# STM32_FillLab_WalkThrough.net
KiCad netlist of a schematic drawn in Altium Designer
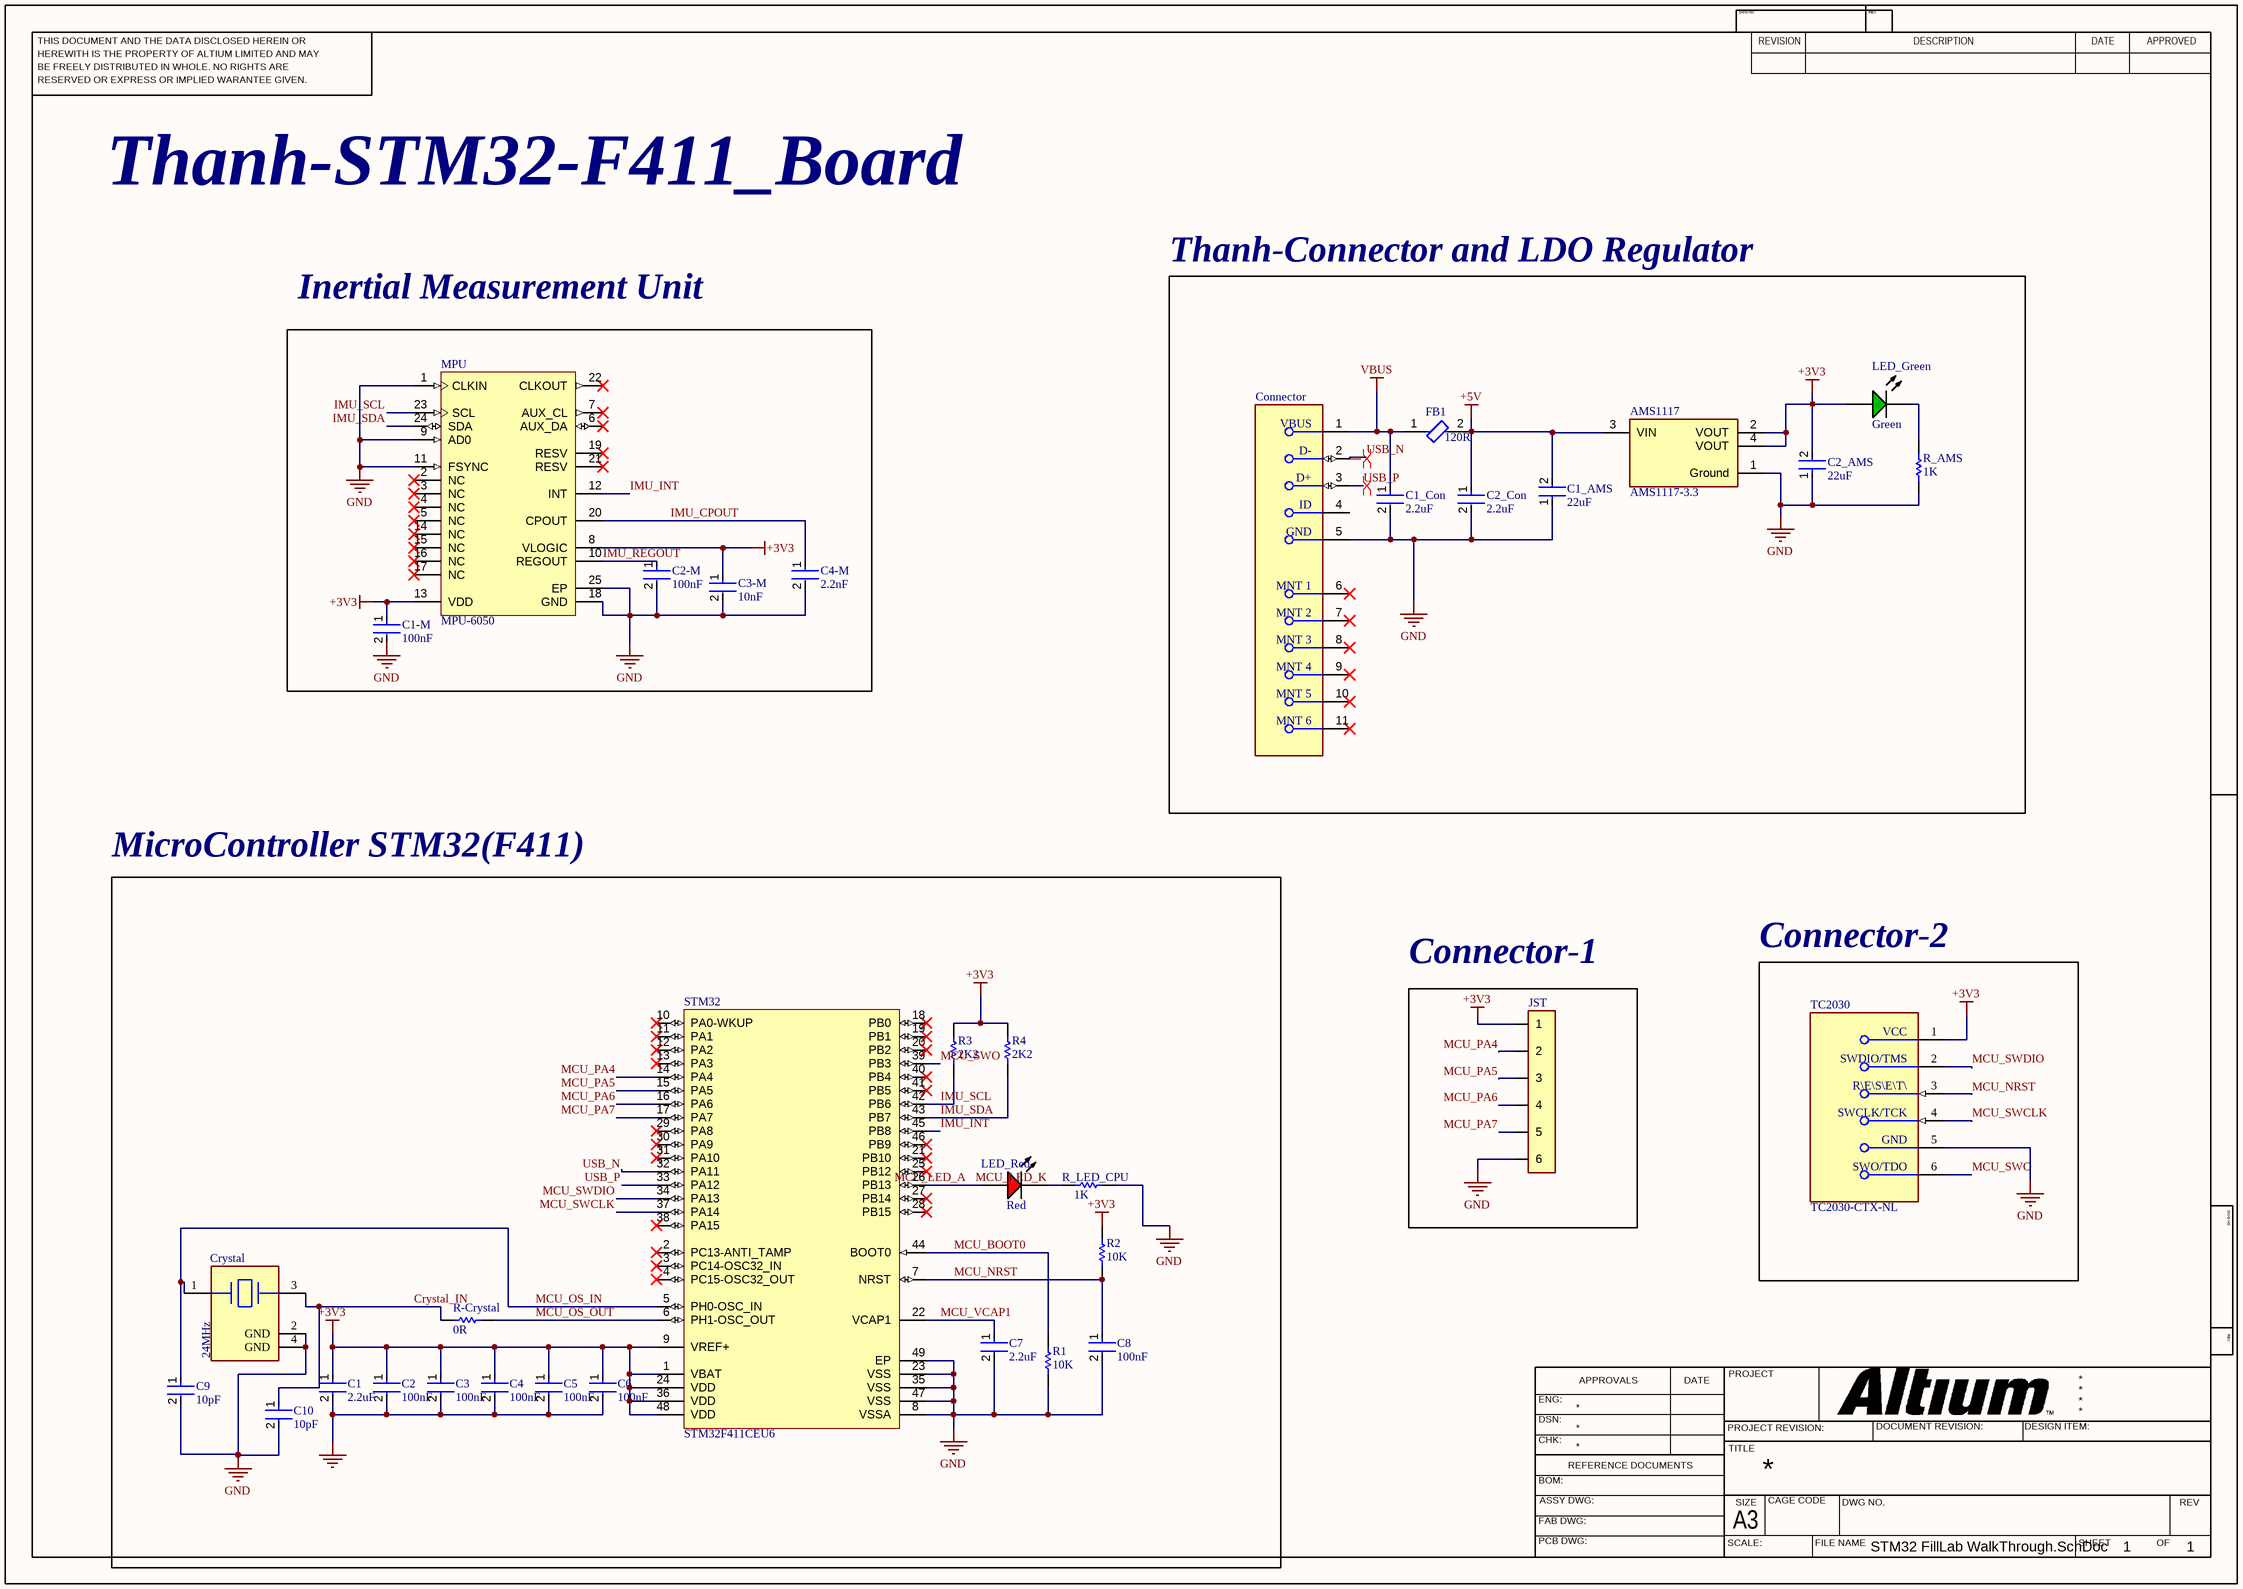
[diagram p0: STM32 FillLab WalkThrough.SchDoc]

(export (version "E")
  (design (tool "Eeschema 10.0.6"))
  (components
    (comp (ref "AMS1117")
      (value "AMS1117-3.3")
      (footprint "FP-AMS1117-IPC_C")
      (description "LDO Voltage Regulators 1A, 3.3V")
      (fields
        (field (name "OCTOPART") "https://octopart.com/ams1117-3.3-advanced+monolithic+systems-25899300")
        (field (name "MANUFACTURER") "Advanced Monolithic Systems")
      )
      (libsource (lib "Altium Content Vault") (part "8bdbb5f8e77002000e30dd2845d0354"))
    )
    (comp (ref "C1")
      (value "2.2uF")
      (footprint "FP-C0402-BB-MFG")
      (description "CAP CER 0.1UF 10V X5R 0402")
      (fields (field (name "MANUFACTURER") "Kemet") (field (name "TOLERANCE") "0.1"))
      (libsource (lib "Altium Content Vault") (part "b4654b650e69147ec39a6b967a45e02"))
    )
    (comp (ref "C1-M")
      (value "100nF")
      (footprint "FP-C0402-BB-MFG")
      (description "CAP CER 0.1UF 10V X5R 0402")
      (fields (field (name "MANUFACTURER") "Kemet") (field (name "TOLERANCE") "0.1"))
      (libsource (lib "Altium Content Vault") (part "b4654b650e69147ec39a6b967a45e02"))
    )
    (comp (ref "C1_AMS")
      (value "22uF")
      (footprint "FP-C0402-BB-MFG")
      (description "CAP CER 0.1UF 10V X5R 0402")
      (fields (field (name "MANUFACTURER") "Kemet") (field (name "TOLERANCE") "0.1"))
      (libsource (lib "Altium Content Vault") (part "b4654b650e69147ec39a6b967a45e02"))
    )
    (comp (ref "C1_Con")
      (value "2.2uF")
      (footprint "FP-C0402-BB-MFG")
      (description "CAP CER 0.1UF 10V X5R 0402")
      (fields (field (name "MANUFACTURER") "Kemet") (field (name "TOLERANCE") "0.1"))
      (libsource (lib "Altium Content Vault") (part "b4654b650e69147ec39a6b967a45e02"))
    )
    (comp (ref "C2")
      (value "100nF")
      (footprint "FP-C0402-BB-MFG")
      (description "CAP CER 0.1UF 10V X5R 0402")
      (fields (field (name "MANUFACTURER") "Kemet") (field (name "TOLERANCE") "0.1"))
      (libsource (lib "Altium Content Vault") (part "b4654b650e69147ec39a6b967a45e02"))
    )
    (comp (ref "C2-M")
      (value "100nF")
      (footprint "FP-C0402-BB-MFG")
      (description "CAP CER 0.1UF 10V X5R 0402")
      (fields (field (name "MANUFACTURER") "Kemet") (field (name "TOLERANCE") "0.1"))
      (libsource (lib "Altium Content Vault") (part "b4654b650e69147ec39a6b967a45e02"))
    )
    (comp (ref "C2_AMS")
      (value "22uF")
      (footprint "FP-C0402-BB-MFG")
      (description "CAP CER 0.1UF 10V X5R 0402")
      (fields (field (name "MANUFACTURER") "Kemet") (field (name "TOLERANCE") "0.1"))
      (libsource (lib "Altium Content Vault") (part "b4654b650e69147ec39a6b967a45e02"))
    )
    (comp (ref "C2_Con")
      (value "2.2uF")
      (footprint "FP-C0402-BB-MFG")
      (description "CAP CER 0.1UF 10V X5R 0402")
      (fields (field (name "MANUFACTURER") "Kemet") (field (name "TOLERANCE") "0.1"))
      (libsource (lib "Altium Content Vault") (part "b4654b650e69147ec39a6b967a45e02"))
    )
    (comp (ref "C3")
      (value "100nF")
      (footprint "FP-C0402-BB-MFG")
      (description "CAP CER 0.1UF 10V X5R 0402")
      (fields (field (name "MANUFACTURER") "Kemet") (field (name "TOLERANCE") "0.1"))
      (libsource (lib "Altium Content Vault") (part "b4654b650e69147ec39a6b967a45e02"))
    )
    (comp (ref "C3-M")
      (value "10nF")
      (footprint "FP-C0402-BB-MFG")
      (description "CAP CER 0.1UF 10V X5R 0402")
      (fields (field (name "MANUFACTURER") "Kemet") (field (name "TOLERANCE") "0.1"))
      (libsource (lib "Altium Content Vault") (part "b4654b650e69147ec39a6b967a45e02"))
    )
    (comp (ref "C4")
      (value "100nF")
      (footprint "FP-C0402-BB-MFG")
      (description "CAP CER 0.1UF 10V X5R 0402")
      (fields (field (name "MANUFACTURER") "Kemet") (field (name "TOLERANCE") "0.1"))
      (libsource (lib "Altium Content Vault") (part "b4654b650e69147ec39a6b967a45e02"))
    )
    (comp (ref "C4-M")
      (value "2.2nF")
      (footprint "FP-C0402-BB-MFG")
      (description "CAP CER 0.1UF 10V X5R 0402")
      (fields (field (name "MANUFACTURER") "Kemet") (field (name "TOLERANCE") "0.1"))
      (libsource (lib "Altium Content Vault") (part "b4654b650e69147ec39a6b967a45e02"))
    )
    (comp (ref "C5")
      (value "100nF")
      (footprint "FP-C0402-BB-MFG")
      (description "CAP CER 0.1UF 10V X5R 0402")
      (fields (field (name "MANUFACTURER") "Kemet") (field (name "TOLERANCE") "0.1"))
      (libsource (lib "Altium Content Vault") (part "b4654b650e69147ec39a6b967a45e02"))
    )
    (comp (ref "C6")
      (value "100nF")
      (footprint "FP-C0402-BB-MFG")
      (description "CAP CER 0.1UF 10V X5R 0402")
      (fields (field (name "MANUFACTURER") "Kemet") (field (name "TOLERANCE") "0.1"))
      (libsource (lib "Altium Content Vault") (part "b4654b650e69147ec39a6b967a45e02"))
    )
    (comp (ref "C7")
      (value "2.2uF")
      (footprint "FP-C0402-BB-MFG")
      (description "CAP CER 0.1UF 10V X5R 0402")
      (fields (field (name "MANUFACTURER") "Kemet") (field (name "TOLERANCE") "0.1"))
      (libsource (lib "Altium Content Vault") (part "b4654b650e69147ec39a6b967a45e02"))
    )
    (comp (ref "C8")
      (value "100nF")
      (footprint "FP-C0402-BB-MFG")
      (description "CAP CER 0.1UF 10V X5R 0402")
      (fields (field (name "MANUFACTURER") "Kemet") (field (name "TOLERANCE") "0.1"))
      (libsource (lib "Altium Content Vault") (part "b4654b650e69147ec39a6b967a45e02"))
    )
    (comp (ref "C9")
      (value "10pF")
      (footprint "FP-C0402-BB-MFG")
      (description "CAP CER 0.1UF 10V X5R 0402")
      (fields (field (name "MANUFACTURER") "Kemet") (field (name "TOLERANCE") "0.1"))
      (libsource (lib "Altium Content Vault") (part "b4654b650e69147ec39a6b967a45e02"))
    )
    (comp (ref "C10")
      (value "10pF")
      (footprint "FP-C0402-BB-MFG")
      (description "CAP CER 0.1UF 10V X5R 0402")
      (fields (field (name "MANUFACTURER") "Kemet") (field (name "TOLERANCE") "0.1"))
      (libsource (lib "Altium Content Vault") (part "b4654b650e69147ec39a6b967a45e02"))
    )
    (comp (ref "Connector")
      (value "473460001")
      (footprint "FP-473460001-MFG")
      (description "CONN RCPT USB2.0 MICRO B SMD R/A")
      (fields
        (field (name "OCTOPART") "https://octopart.com/47346-0001-molex-7164928")
        (field (name "MANUFACTURER") "Molex")
      )
      (libsource (lib "Altium Content Vault") (part "53ae1f1d9b557310b43ca686e5bb76a"))
    )
    (comp (ref "Crystal")
      (value "24MHz")
      (footprint "FP-ABM8-MFG")
      (description "Crystal 24MHz ±20ppm 18pF SMD-4 3.2mm x 2.5mm")
      (fields (field (name "TOLERANCE") "20ppm"))
      (libsource (lib "Altium Content Vault") (part "dfdb7f9a12507849fb681da9a70121c"))
    )
    (comp (ref "FB1")
      (value "120R")
      (footprint "FP-BLM15-0_05-IPC_B")
      (description "Chip Ferrite Bead, 0402, 1000Ω @ 100MHz, 0.65Ω, 25%, 300mA")
      (fields (field (name "TOLERANCE") "25%"))
      (libsource (lib "Altium Content Vault") (part "5f30dd21d616792df468990f7003faa"))
    )
    (comp (ref "JST")
      (value "SM06B-GHS-TB")
      (footprint "JST-GH-6")
      (description "Connector Header Surface Mount, Right Angle 6 position 0.049 (1.25mm)")
      (fields (field (name "MF") "JST Sales"))
      (libsource (lib "SM06B-GHS-TB") (part "SM06B-GHS-TB"))
    )
    (comp (ref "LED_Green")
      (value "Green")
      (footprint "AVAG-HSMX-C170_V")
      (description "Chip LED, Green, 2.2 V, -40 to 85 degC, 2-Pin SMD, Pb-Free, Tape and Reel")
      (fields (field (name "MANUFACTURER") "Avago"))
      (libsource (lib "Altium Content Vault") (part "LED_GREEN_A1K2-2"))
    )
    (comp (ref "LED_Red")
      (value "Red")
      (footprint "AVAG-HSMX-C150_V")
      (description "LED Uni-Color Red, 65 mW, 25 mA, -40 to 85 degC, 2-Pin SMD, RoHS, Tape and Reel")
      (fields (field (name "MANUFACTURER") "Avago"))
      (libsource (lib "Altium Content Vault") (part "LED-RED-AK-2"))
    )
    (comp (ref "MPU")
      (value "MPU-6050")
      (footprint "IS-QFN-24_V")
      (fields (field (name "MANUFACTURER") "InvenSense"))
      (libsource (lib "Altium Content Vault") (part "IS-MPU-6050-QFN-24"))
    )
    (comp (ref "R-Crystal")
      (value "0R")
      (footprint "RESC1609X50X30NL8T20")
      (description "Chip Resistor, 10 KOhm, +/- 1%, 100 mW, -55 to 155 degC, 0603 (1608 Metric), RoHS, Tape and Reel")
      (fields (field (name "MANUFACTURER") "Vishay Semiconductor"))
      (libsource (lib "Altium Content Vault") (part "RES-2"))
    )
    (comp (ref "R1")
      (value "10K")
      (footprint "RESC1609X50X30NL8T20")
      (description "Chip Resistor, 10 KOhm, +/- 1%, 100 mW, -55 to 155 degC, 0603 (1608 Metric), RoHS, Tape and Reel")
      (fields (field (name "MANUFACTURER") "Vishay Semiconductor"))
      (libsource (lib "Altium Content Vault") (part "RES-2"))
    )
    (comp (ref "R2")
      (value "10K")
      (footprint "RESC1609X50X30NL8T20")
      (description "Chip Resistor, 10 KOhm, +/- 1%, 100 mW, -55 to 155 degC, 0603 (1608 Metric), RoHS, Tape and Reel")
      (fields (field (name "MANUFACTURER") "Vishay Semiconductor"))
      (libsource (lib "Altium Content Vault") (part "RES-2"))
    )
    (comp (ref "R3")
      (value "2K2")
      (footprint "RESC1609X50X30NL8T20")
      (description "Chip Resistor, 10 KOhm, +/- 1%, 100 mW, -55 to 155 degC, 0603 (1608 Metric), RoHS, Tape and Reel")
      (fields (field (name "MANUFACTURER") "Vishay Semiconductor"))
      (libsource (lib "Altium Content Vault") (part "RES-2"))
    )
    (comp (ref "R4")
      (value "2K2")
      (footprint "RESC1609X50X30NL8T20")
      (description "Chip Resistor, 10 KOhm, +/- 1%, 100 mW, -55 to 155 degC, 0603 (1608 Metric), RoHS, Tape and Reel")
      (fields (field (name "MANUFACTURER") "Vishay Semiconductor"))
      (libsource (lib "Altium Content Vault") (part "RES-2"))
    )
    (comp (ref "R_AMS")
      (value "1K")
      (footprint "RESC1609X50X30NL8T20")
      (description "Chip Resistor, 10 KOhm, +/- 1%, 100 mW, -55 to 155 degC, 0603 (1608 Metric), RoHS, Tape and Reel")
      (fields (field (name "MANUFACTURER") "Vishay Semiconductor"))
      (libsource (lib "Altium Content Vault") (part "RES-2"))
    )
    (comp (ref "R_LED_CPU")
      (value "1K")
      (footprint "RESC1609X50X30NL8T20")
      (description "Chip Resistor, 10 KOhm, +/- 1%, 100 mW, -55 to 155 degC, 0603 (1608 Metric), RoHS, Tape and Reel")
      (fields (field (name "MANUFACTURER") "Vishay Semiconductor"))
      (libsource (lib "Altium Content Vault") (part "RES-2"))
    )
    (comp (ref "STM32")
      (value "STM32F411CEU6")
      (footprint "STM-UFQFPN48_L")
      (libsource (lib "Altium Content Vault") (part "MC-ARM-STM32F411-UFQFPN48"))
    )
    (comp (ref "TC2030")
      (value "TC2030-CTX-NL")
      (footprint "FP-TC2030-CTX-NL-MFG")
      (description "6-Pin “No legs” TC2030 Plug-of-Nails™ Cable for use with ARM Cortex processors")
      (libsource (lib "Altium Content Vault") (part "e3fe093a55dc37473f431e03719485e"))
    )
  )
  (nets
    (net (code "1") (name "+3V3") (class "Default")
      (node (ref "AMS1117") (pin "2") (pinfunction "VOUT_2") (pintype "passive"))
      (node (ref "AMS1117") (pin "4") (pinfunction "VOUT_4") (pintype "passive"))
      (node (ref "C1") (pin "1") (pinfunction "1_1") (pintype "passive"))
      (node (ref "C1-M") (pin "1") (pinfunction "1_1") (pintype "passive"))
      (node (ref "C2") (pin "1") (pinfunction "1_1") (pintype "passive"))
      (node (ref "C2_AMS") (pin "2") (pinfunction "2_2") (pintype "passive"))
      (node (ref "C3") (pin "1") (pinfunction "1_1") (pintype "passive"))
      (node (ref "C3-M") (pin "1") (pinfunction "1_1") (pintype "passive"))
      (node (ref "C4") (pin "1") (pinfunction "1_1") (pintype "passive"))
      (node (ref "C5") (pin "1") (pinfunction "1_1") (pintype "passive"))
      (node (ref "C6") (pin "1") (pinfunction "1_1") (pintype "passive"))
      (node (ref "JST") (pin "P$1") (pinfunction "1_P$1") (pintype "passive"))
      (node (ref "LED_Green") (pin "1") (pinfunction "A_1") (pintype "passive"))
      (node (ref "MPU") (pin "13") (pinfunction "VDD_13") (pintype "power_in"))
      (node (ref "MPU") (pin "8") (pinfunction "VLOGIC_8") (pintype "power_in"))
      (node (ref "R2") (pin "2") (pinfunction "2_2") (pintype "passive"))
      (node (ref "R3") (pin "2") (pinfunction "2_2") (pintype "passive"))
      (node (ref "R4") (pin "2") (pinfunction "2_2") (pintype "passive"))
      (node (ref "STM32") (pin "1") (pinfunction "VBAT_1") (pintype "power_in"))
      (node (ref "STM32") (pin "24") (pinfunction "VDD_24") (pintype "power_in"))
      (node (ref "STM32") (pin "36") (pinfunction "VDD_36") (pintype "power_in"))
      (node (ref "STM32") (pin "48") (pinfunction "VDD_48") (pintype "power_in"))
      (node (ref "STM32") (pin "9") (pinfunction "VREF+_9") (pintype "power_in"))
      (node (ref "TC2030") (pin "1") (pinfunction "VCC_1") (pintype "power_in"))
    )
    (net (code "2") (name "+5V") (class "Default")
      (node (ref "AMS1117") (pin "3") (pinfunction "VIN_3") (pintype "power_in"))
      (node (ref "C1_AMS") (pin "2") (pinfunction "2_2") (pintype "passive"))
      (node (ref "C2_Con") (pin "1") (pinfunction "1_1") (pintype "passive"))
      (node (ref "FB1") (pin "2") (pinfunction "2_2") (pintype "passive"))
    )
    (net (code "3") (name "/Crystal_IN") (class "Default")
      (node (ref "C10") (pin "1") (pinfunction "1_1") (pintype "passive"))
      (node (ref "Crystal") (pin "3") (pinfunction "3_3") (pintype "passive"))
      (node (ref "R-Crystal") (pin "2") (pinfunction "2_2") (pintype "passive"))
    )
    (net (code "4") (name "/IMU_CPOUT") (class "Default")
      (node (ref "C4-M") (pin "1") (pinfunction "1_1") (pintype "passive"))
      (node (ref "MPU") (pin "20") (pinfunction "CPOUT_20") (pintype "passive"))
    )
    (net (code "5") (name "/IMU_INT") (class "Default")
      (node (ref "MPU") (pin "12") (pinfunction "INT_12") (pintype "open_collector"))
      (node (ref "STM32") (pin "45") (pinfunction "PB8_45") (pintype "bidirectional"))
    )
    (net (code "6") (name "/IMU_REGOUT") (class "Default")
      (node (ref "C2-M") (pin "1") (pinfunction "1_1") (pintype "passive"))
      (node (ref "MPU") (pin "10") (pinfunction "REGOUT_10") (pintype "passive"))
    )
    (net (code "7") (name "/IMU_SCL") (class "Default")
      (node (ref "MPU") (pin "23") (pinfunction "SCL_23") (pintype "input"))
      (node (ref "R3") (pin "1") (pinfunction "1_1") (pintype "passive"))
      (node (ref "STM32") (pin "42") (pinfunction "PB6_42") (pintype "bidirectional"))
    )
    (net (code "8") (name "/IMU_SDA") (class "Default")
      (node (ref "MPU") (pin "24") (pinfunction "SDA_24") (pintype "bidirectional"))
      (node (ref "R4") (pin "1") (pinfunction "1_1") (pintype "passive"))
      (node (ref "STM32") (pin "43") (pinfunction "PB7_43") (pintype "bidirectional"))
    )
    (net (code "9") (name "/MCU_BOOT0") (class "Default")
      (node (ref "R1") (pin "2") (pinfunction "2_2") (pintype "passive"))
      (node (ref "STM32") (pin "44") (pinfunction "BOOT0_44") (pintype "input"))
    )
    (net (code "10") (name "/MCU_LED_A") (class "Default")
      (node (ref "LED_Red") (pin "1") (pinfunction "A_1") (pintype "passive"))
      (node (ref "STM32") (pin "26") (pinfunction "PB13_26") (pintype "bidirectional"))
    )
    (net (code "11") (name "/MCU_LED_K") (class "Default")
      (node (ref "LED_Red") (pin "2") (pinfunction "K_2") (pintype "passive"))
      (node (ref "R_LED_CPU") (pin "2") (pinfunction "2_2") (pintype "passive"))
    )
    (net (code "12") (name "/MCU_NRST") (class "Default")
      (node (ref "C8") (pin "1") (pinfunction "1_1") (pintype "passive"))
      (node (ref "R2") (pin "1") (pinfunction "1_1") (pintype "passive"))
      (node (ref "STM32") (pin "7") (pinfunction "NRST_7") (pintype "bidirectional"))
      (node (ref "TC2030") (pin "3") (pinfunction "~{RESET}_3") (pintype "input"))
    )
    (net (code "13") (name "/MCU_OS_IN") (class "Default")
      (node (ref "C9") (pin "1") (pinfunction "1_1") (pintype "passive"))
      (node (ref "Crystal") (pin "1") (pinfunction "1_1") (pintype "passive"))
      (node (ref "STM32") (pin "5") (pinfunction "PH0-OSC_IN_5") (pintype "bidirectional"))
    )
    (net (code "14") (name "/MCU_OS_OUT") (class "Default")
      (node (ref "R-Crystal") (pin "1") (pinfunction "1_1") (pintype "passive"))
      (node (ref "STM32") (pin "6") (pinfunction "PH1-OSC_OUT_6") (pintype "bidirectional"))
    )
    (net (code "15") (name "/MCU_PA4") (class "Default")
      (node (ref "JST") (pin "P$2") (pinfunction "2_P$2") (pintype "passive"))
      (node (ref "STM32") (pin "14") (pinfunction "PA4_14") (pintype "bidirectional"))
    )
    (net (code "16") (name "/MCU_PA5") (class "Default")
      (node (ref "JST") (pin "P$3") (pinfunction "3_P$3") (pintype "passive"))
      (node (ref "STM32") (pin "15") (pinfunction "PA5_15") (pintype "bidirectional"))
    )
    (net (code "17") (name "/MCU_PA6") (class "Default")
      (node (ref "JST") (pin "P$4") (pinfunction "4_P$4") (pintype "passive"))
      (node (ref "STM32") (pin "16") (pinfunction "PA6_16") (pintype "bidirectional"))
    )
    (net (code "18") (name "/MCU_PA7") (class "Default")
      (node (ref "JST") (pin "P$5") (pinfunction "5_P$5") (pintype "passive"))
      (node (ref "STM32") (pin "17") (pinfunction "PA7_17") (pintype "bidirectional"))
    )
    (net (code "19") (name "/MCU_SWCLK") (class "Default")
      (node (ref "STM32") (pin "37") (pinfunction "PA14_37") (pintype "bidirectional"))
      (node (ref "TC2030") (pin "4") (pinfunction "SWCLK/TCK_4") (pintype "input"))
    )
    (net (code "20") (name "/MCU_SWDIO") (class "Default")
      (node (ref "STM32") (pin "34") (pinfunction "PA13_34") (pintype "bidirectional"))
      (node (ref "TC2030") (pin "2") (pinfunction "SWDIO/TMS_2") (pintype "passive"))
    )
    (net (code "21") (name "/MCU_SWO") (class "Default")
      (node (ref "STM32") (pin "39") (pinfunction "PB3_39") (pintype "bidirectional"))
      (node (ref "TC2030") (pin "6") (pinfunction "SWO/TDO_6") (pintype "passive"))
    )
    (net (code "22") (name "/MCU_VCAP1") (class "Default")
      (node (ref "C7") (pin "1") (pinfunction "1_1") (pintype "passive"))
      (node (ref "STM32") (pin "22") (pinfunction "VCAP1_22") (pintype "passive"))
    )
    (net (code "23") (name "/USB_N") (class "Default")
      (node (ref "Connector") (pin "2") (pinfunction "D-_2") (pintype "bidirectional"))
      (node (ref "STM32") (pin "32") (pinfunction "PA11_32") (pintype "bidirectional"))
    )
    (net (code "24") (name "/USB_P") (class "Default")
      (node (ref "Connector") (pin "3") (pinfunction "D+_3") (pintype "bidirectional"))
      (node (ref "STM32") (pin "33") (pinfunction "PA12_33") (pintype "bidirectional"))
    )
    (net (code "25") (name "GND") (class "Default")
      (node (ref "AMS1117") (pin "1") (pinfunction "Ground_1") (pintype "power_in"))
      (node (ref "C1") (pin "2") (pinfunction "2_2") (pintype "passive"))
      (node (ref "C1-M") (pin "2") (pinfunction "2_2") (pintype "passive"))
      (node (ref "C10") (pin "2") (pinfunction "2_2") (pintype "passive"))
      (node (ref "C1_AMS") (pin "1") (pinfunction "1_1") (pintype "passive"))
      (node (ref "C1_Con") (pin "2") (pinfunction "2_2") (pintype "passive"))
      (node (ref "C2") (pin "2") (pinfunction "2_2") (pintype "passive"))
      (node (ref "C2-M") (pin "2") (pinfunction "2_2") (pintype "passive"))
      (node (ref "C2_AMS") (pin "1") (pinfunction "1_1") (pintype "passive"))
      (node (ref "C2_Con") (pin "2") (pinfunction "2_2") (pintype "passive"))
      (node (ref "C3") (pin "2") (pinfunction "2_2") (pintype "passive"))
      (node (ref "C3-M") (pin "2") (pinfunction "2_2") (pintype "passive"))
      (node (ref "C4") (pin "2") (pinfunction "2_2") (pintype "passive"))
      (node (ref "C4-M") (pin "2") (pinfunction "2_2") (pintype "passive"))
      (node (ref "C5") (pin "2") (pinfunction "2_2") (pintype "passive"))
      (node (ref "C6") (pin "2") (pinfunction "2_2") (pintype "passive"))
      (node (ref "C7") (pin "2") (pinfunction "2_2") (pintype "passive"))
      (node (ref "C8") (pin "2") (pinfunction "2_2") (pintype "passive"))
      (node (ref "C9") (pin "2") (pinfunction "2_2") (pintype "passive"))
      (node (ref "Connector") (pin "5") (pinfunction "GND_5") (pintype "power_in"))
      (node (ref "Crystal") (pin "2") (pinfunction "GND_2") (pintype "power_in"))
      (node (ref "Crystal") (pin "4") (pinfunction "GND_4") (pintype "power_in"))
      (node (ref "JST") (pin "P$6") (pinfunction "6_P$6") (pintype "passive"))
      (node (ref "MPU") (pin "1") (pinfunction "CLKIN_1") (pintype "input"))
      (node (ref "MPU") (pin "11") (pinfunction "FSYNC_11") (pintype "input"))
      (node (ref "MPU") (pin "18") (pinfunction "GND_18") (pintype "power_in"))
      (node (ref "MPU") (pin "25") (pinfunction "EP_25") (pintype "power_in"))
      (node (ref "MPU") (pin "9") (pinfunction "AD0_9") (pintype "input"))
      (node (ref "R1") (pin "1") (pinfunction "1_1") (pintype "passive"))
      (node (ref "R_AMS") (pin "1") (pinfunction "1_1") (pintype "passive"))
      (node (ref "R_LED_CPU") (pin "1") (pinfunction "1_1") (pintype "passive"))
      (node (ref "STM32") (pin "23") (pinfunction "VSS_23") (pintype "power_in"))
      (node (ref "STM32") (pin "35") (pinfunction "VSS_35") (pintype "power_in"))
      (node (ref "STM32") (pin "47") (pinfunction "VSS_47") (pintype "power_in"))
      (node (ref "STM32") (pin "49") (pinfunction "EP_49") (pintype "power_in"))
      (node (ref "STM32") (pin "8") (pinfunction "VSSA_8") (pintype "power_in"))
      (node (ref "TC2030") (pin "5") (pinfunction "GND_5") (pintype "power_in"))
    )
    (net (code "26") (name "Net-(LED_Green-K)") (class "Default")
      (node (ref "LED_Green") (pin "2") (pinfunction "K_2") (pintype "passive"))
      (node (ref "R_AMS") (pin "2") (pinfunction "2_2") (pintype "passive"))
    )
    (net (code "27") (name "VBUS") (class "Default")
      (node (ref "C1_Con") (pin "1") (pinfunction "1_1") (pintype "passive"))
      (node (ref "Connector") (pin "1") (pinfunction "VBUS_1") (pintype "power_in"))
      (node (ref "FB1") (pin "1") (pinfunction "1_1") (pintype "passive"))
    )
    (net (code "28") (name "unconnected-(Connector-ID-Pad4)") (class "Default")
      (node (ref "Connector") (pin "4") (pinfunction "ID_4") (pintype "passive"))
    )
    (net (code "29") (name "unconnected-(Connector-MNT_1-Pad6)") (class "Default")
      (node (ref "Connector") (pin "6") (pinfunction "MNT_1_6") (pintype "passive+no_connect"))
    )
    (net (code "30") (name "unconnected-(Connector-MNT_2-Pad7)") (class "Default")
      (node (ref "Connector") (pin "7") (pinfunction "MNT_2_7") (pintype "passive+no_connect"))
    )
    (net (code "31") (name "unconnected-(Connector-MNT_3-Pad8)") (class "Default")
      (node (ref "Connector") (pin "8") (pinfunction "MNT_3_8") (pintype "passive+no_connect"))
    )
    (net (code "32") (name "unconnected-(Connector-MNT_4-Pad9)") (class "Default")
      (node (ref "Connector") (pin "9") (pinfunction "MNT_4_9") (pintype "passive+no_connect"))
    )
    (net (code "33") (name "unconnected-(Connector-MNT_5-Pad10)") (class "Default")
      (node (ref "Connector") (pin "10") (pinfunction "MNT_5_10") (pintype "passive+no_connect"))
    )
    (net (code "34") (name "unconnected-(Connector-MNT_6-Pad11)") (class "Default")
      (node (ref "Connector") (pin "11") (pinfunction "MNT_6_11") (pintype "passive+no_connect"))
    )
    (net (code "35") (name "unconnected-(MPU-AUX_CL-Pad7)") (class "Default")
      (node (ref "MPU") (pin "7") (pinfunction "AUX_CL_7") (pintype "output+no_connect"))
    )
    (net (code "36") (name "unconnected-(MPU-AUX_DA-Pad6)") (class "Default")
      (node (ref "MPU") (pin "6") (pinfunction "AUX_DA_6") (pintype "bidirectional+no_connect"))
    )
    (net (code "37") (name "unconnected-(MPU-CLKOUT-Pad22)") (class "Default")
      (node (ref "MPU") (pin "22") (pinfunction "CLKOUT_22") (pintype "output+no_connect"))
    )
    (net (code "38") (name "unconnected-(MPU-NC-Pad2)") (class "Default")
      (node (ref "MPU") (pin "2") (pinfunction "NC_2") (pintype "passive+no_connect"))
    )
    (net (code "39") (name "unconnected-(MPU-NC-Pad3)") (class "Default")
      (node (ref "MPU") (pin "3") (pinfunction "NC_3") (pintype "passive+no_connect"))
    )
    (net (code "40") (name "unconnected-(MPU-NC-Pad4)") (class "Default")
      (node (ref "MPU") (pin "4") (pinfunction "NC_4") (pintype "passive+no_connect"))
    )
    (net (code "41") (name "unconnected-(MPU-NC-Pad5)") (class "Default")
      (node (ref "MPU") (pin "5") (pinfunction "NC_5") (pintype "passive+no_connect"))
    )
    (net (code "42") (name "unconnected-(MPU-NC-Pad14)") (class "Default")
      (node (ref "MPU") (pin "14") (pinfunction "NC_14") (pintype "passive+no_connect"))
    )
    (net (code "43") (name "unconnected-(MPU-NC-Pad15)") (class "Default")
      (node (ref "MPU") (pin "15") (pinfunction "NC_15") (pintype "passive+no_connect"))
    )
    (net (code "44") (name "unconnected-(MPU-NC-Pad16)") (class "Default")
      (node (ref "MPU") (pin "16") (pinfunction "NC_16") (pintype "passive+no_connect"))
    )
    (net (code "45") (name "unconnected-(MPU-NC-Pad17)") (class "Default")
      (node (ref "MPU") (pin "17") (pinfunction "NC_17") (pintype "passive+no_connect"))
    )
    (net (code "46") (name "unconnected-(MPU-RESV-Pad19)") (class "Default")
      (node (ref "MPU") (pin "19") (pinfunction "RESV_19") (pintype "passive+no_connect"))
    )
    (net (code "47") (name "unconnected-(MPU-RESV-Pad21)") (class "Default")
      (node (ref "MPU") (pin "21") (pinfunction "RESV_21") (pintype "passive+no_connect"))
    )
    (net (code "48") (name "unconnected-(STM32-PA0-WKUP-Pad10)") (class "Default")
      (node (ref "STM32") (pin "10") (pinfunction "PA0-WKUP_10") (pintype "bidirectional+no_connect"))
    )
    (net (code "49") (name "unconnected-(STM32-PA1-Pad11)") (class "Default")
      (node (ref "STM32") (pin "11") (pinfunction "PA1_11") (pintype "bidirectional+no_connect"))
    )
    (net (code "50") (name "unconnected-(STM32-PA2-Pad12)") (class "Default")
      (node (ref "STM32") (pin "12") (pinfunction "PA2_12") (pintype "bidirectional+no_connect"))
    )
    (net (code "51") (name "unconnected-(STM32-PA3-Pad13)") (class "Default")
      (node (ref "STM32") (pin "13") (pinfunction "PA3_13") (pintype "bidirectional+no_connect"))
    )
    (net (code "52") (name "unconnected-(STM32-PA8-Pad29)") (class "Default")
      (node (ref "STM32") (pin "29") (pinfunction "PA8_29") (pintype "bidirectional+no_connect"))
    )
    (net (code "53") (name "unconnected-(STM32-PA9-Pad30)") (class "Default")
      (node (ref "STM32") (pin "30") (pinfunction "PA9_30") (pintype "bidirectional+no_connect"))
    )
    (net (code "54") (name "unconnected-(STM32-PA10-Pad31)") (class "Default")
      (node (ref "STM32") (pin "31") (pinfunction "PA10_31") (pintype "bidirectional+no_connect"))
    )
    (net (code "55") (name "unconnected-(STM32-PA15-Pad38)") (class "Default")
      (node (ref "STM32") (pin "38") (pinfunction "PA15_38") (pintype "bidirectional+no_connect"))
    )
    (net (code "56") (name "unconnected-(STM32-PB0-Pad18)") (class "Default")
      (node (ref "STM32") (pin "18") (pinfunction "PB0_18") (pintype "bidirectional+no_connect"))
    )
    (net (code "57") (name "unconnected-(STM32-PB1-Pad19)") (class "Default")
      (node (ref "STM32") (pin "19") (pinfunction "PB1_19") (pintype "bidirectional+no_connect"))
    )
    (net (code "58") (name "unconnected-(STM32-PB2-Pad20)") (class "Default")
      (node (ref "STM32") (pin "20") (pinfunction "PB2_20") (pintype "bidirectional+no_connect"))
    )
    (net (code "59") (name "unconnected-(STM32-PB4-Pad40)") (class "Default")
      (node (ref "STM32") (pin "40") (pinfunction "PB4_40") (pintype "bidirectional+no_connect"))
    )
    (net (code "60") (name "unconnected-(STM32-PB5-Pad41)") (class "Default")
      (node (ref "STM32") (pin "41") (pinfunction "PB5_41") (pintype "bidirectional+no_connect"))
    )
    (net (code "61") (name "unconnected-(STM32-PB9-Pad46)") (class "Default")
      (node (ref "STM32") (pin "46") (pinfunction "PB9_46") (pintype "bidirectional+no_connect"))
    )
    (net (code "62") (name "unconnected-(STM32-PB10-Pad21)") (class "Default")
      (node (ref "STM32") (pin "21") (pinfunction "PB10_21") (pintype "bidirectional+no_connect"))
    )
    (net (code "63") (name "unconnected-(STM32-PB12-Pad25)") (class "Default")
      (node (ref "STM32") (pin "25") (pinfunction "PB12_25") (pintype "bidirectional+no_connect"))
    )
    (net (code "64") (name "unconnected-(STM32-PB14-Pad27)") (class "Default")
      (node (ref "STM32") (pin "27") (pinfunction "PB14_27") (pintype "bidirectional+no_connect"))
    )
    (net (code "65") (name "unconnected-(STM32-PB15-Pad28)") (class "Default")
      (node (ref "STM32") (pin "28") (pinfunction "PB15_28") (pintype "bidirectional+no_connect"))
    )
    (net (code "66") (name "unconnected-(STM32-PC13-ANTI_TAMP-Pad2)") (class "Default")
      (node (ref "STM32") (pin "2") (pinfunction "PC13-ANTI_TAMP_2") (pintype "bidirectional+no_connect"))
    )
    (net (code "67") (name "unconnected-(STM32-PC14-OSC32_IN-Pad3)") (class "Default")
      (node (ref "STM32") (pin "3") (pinfunction "PC14-OSC32_IN_3") (pintype "bidirectional+no_connect"))
    )
    (net (code "68") (name "unconnected-(STM32-PC15-OSC32_OUT-Pad4)") (class "Default")
      (node (ref "STM32") (pin "4") (pinfunction "PC15-OSC32_OUT_4") (pintype "bidirectional+no_connect"))
    )
  )
)
